# Main.net
KiCad netlist of a schematic drawn in Altium Designer
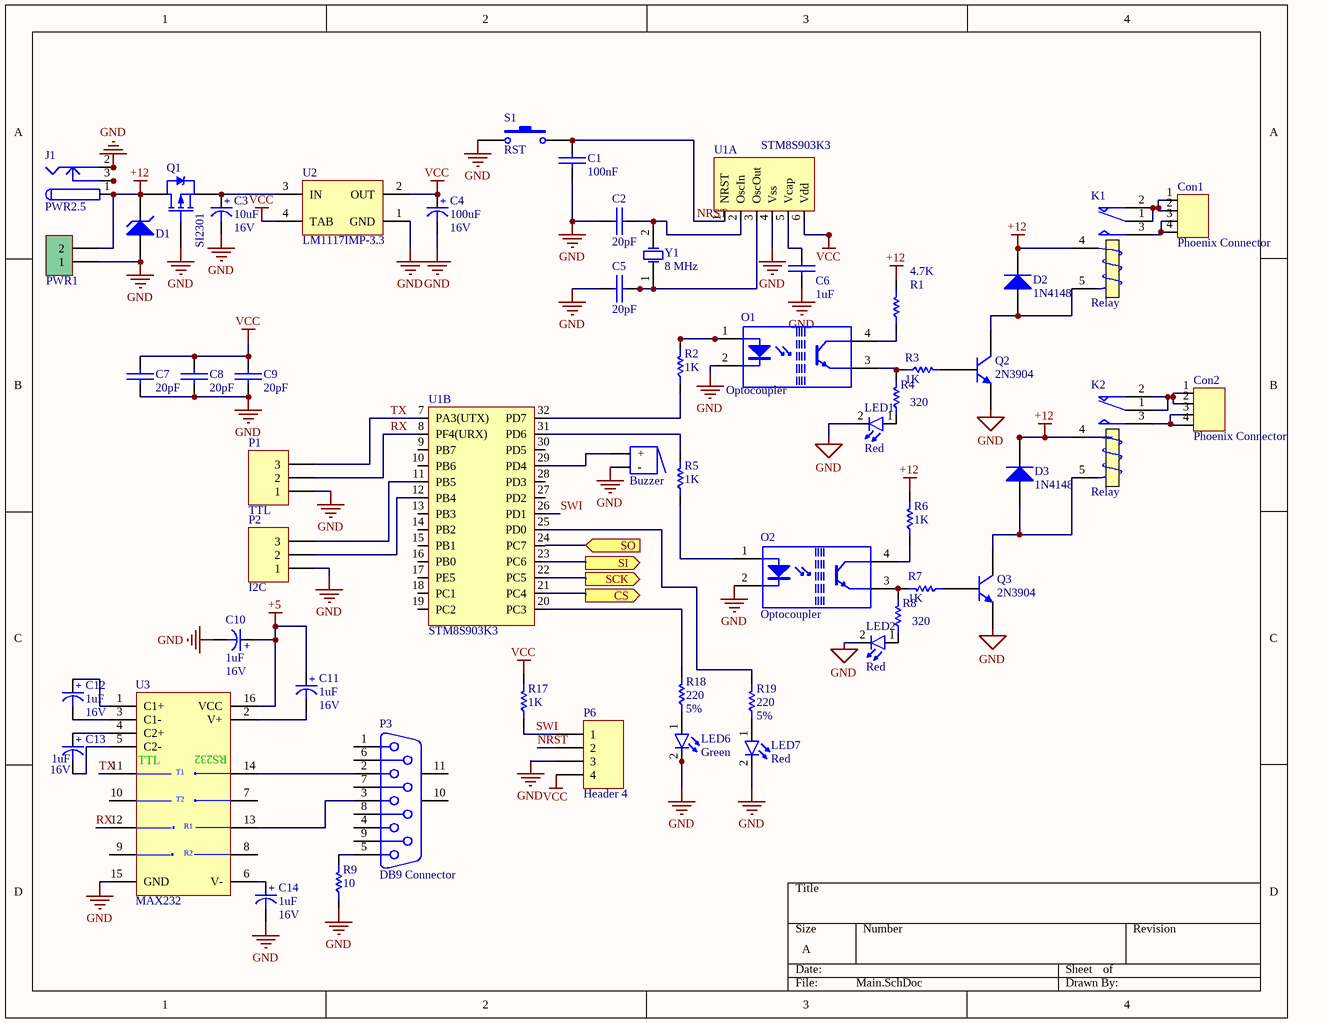
[diagram p0: Main.SchDoc]

(export (version "E")
  (design (tool "Eeschema 10.0.6"))
  (components
    (comp (ref "Buzzer")
      (value "Buzzer")
      (footprint "BUZZER")
      (fields (field (name "DESIGNER") "Seyed Mohsen Ghasemain"))
      (libsource (lib "usefully_Library") (part "Buzzer"))
    )
    (comp (ref "C1")
      (value "100nF")
      (footprint "SMD_CAP_1206")
      (description "Bipolar Capacitor")
      (fields (field (name "VOLTAGE") "100V") (field (name "DESIGNER") "Saeid Jorablo"))
      (libsource (lib "My_Library") (part "Cap-Bipolar"))
    )
    (comp (ref "C2")
      (value "20pF")
      (footprint "SMD_CAP_1206")
      (description "Bipolar Capacitor")
      (fields (field (name "VOLTAGE") "100V") (field (name "DESIGNER") "Saeid Jorablo"))
      (libsource (lib "My_Library") (part "Cap-Bipolar"))
    )
    (comp (ref "C3")
      (value "10uF")
      (footprint "CAPP 1206 (3216X18L) Size A")
      (description "Polar Capacitor")
      (fields (field (name "VOLTAGE") "16V") (field (name "DESIGNER") "Saeid Jorablo"))
      (libsource (lib "My_Library") (part "Cap-Polar"))
    )
    (comp (ref "C4")
      (value "100uF")
      (footprint "CAPP 1206 (3216X18L) Size A")
      (description "Polar Capacitor")
      (fields (field (name "VOLTAGE") "16V") (field (name "DESIGNER") "Saeid Jorablo"))
      (libsource (lib "My_Library") (part "Cap-Polar"))
    )
    (comp (ref "C5")
      (value "20pF")
      (footprint "SMD_CAP_1206")
      (description "Bipolar Capacitor")
      (fields (field (name "VOLTAGE") "100V") (field (name "DESIGNER") "Saeid Jorablo"))
      (libsource (lib "My_Library") (part "Cap-Bipolar"))
    )
    (comp (ref "C6")
      (value "1uF")
      (footprint "SMD_CAP_1206")
      (description "Bipolar Capacitor")
      (fields (field (name "VOLTAGE") "100V") (field (name "DESIGNER") "Saeid Jorablo"))
      (libsource (lib "My_Library") (part "Cap-Bipolar"))
    )
    (comp (ref "C7")
      (value "20pF")
      (footprint "SMD_CAP_1206")
      (description "Bipolar Capacitor")
      (fields (field (name "VOLTAGE") "100V") (field (name "DESIGNER") "Saeid Jorablo"))
      (libsource (lib "My_Library") (part "Cap-Bipolar"))
    )
    (comp (ref "C8")
      (value "20pF")
      (footprint "SMD_CAP_1206")
      (description "Bipolar Capacitor")
      (fields (field (name "VOLTAGE") "100V") (field (name "DESIGNER") "Saeid Jorablo"))
      (libsource (lib "My_Library") (part "Cap-Bipolar"))
    )
    (comp (ref "C9")
      (value "20pF")
      (footprint "SMD_CAP_1206")
      (description "Bipolar Capacitor")
      (fields (field (name "VOLTAGE") "100V") (field (name "DESIGNER") "Saeid Jorablo"))
      (libsource (lib "My_Library") (part "Cap-Bipolar"))
    )
    (comp (ref "C10")
      (value "1uF")
      (footprint "cap 01")
      (description "Polar Capacitor")
      (fields (field (name "VOLTAGE") "16V") (field (name "DESIGNER") "Saeid Jorablo"))
      (libsource (lib "My_Library") (part "Cap-Polar"))
    )
    (comp (ref "C11")
      (value "1uF")
      (footprint "cap 01")
      (description "Polar Capacitor")
      (fields (field (name "VOLTAGE") "16V") (field (name "DESIGNER") "Saeid Jorablo"))
      (libsource (lib "My_Library") (part "Cap-Polar"))
    )
    (comp (ref "C12")
      (value "1uF")
      (footprint "cap 01")
      (description "Polar Capacitor")
      (fields (field (name "VOLTAGE") "16V") (field (name "DESIGNER") "Saeid Jorablo"))
      (libsource (lib "My_Library") (part "Cap-Polar"))
    )
    (comp (ref "C13")
      (value "1uF")
      (footprint "cap 01")
      (description "Polar Capacitor")
      (fields (field (name "VOLTAGE") "16V") (field (name "DESIGNER") "Saeid Jorablo"))
      (libsource (lib "My_Library") (part "Cap-Polar"))
    )
    (comp (ref "C14")
      (value "1uF")
      (footprint "CAPP 1206 (3216X18L) Size A")
      (description "Polar Capacitor")
      (fields (field (name "VOLTAGE") "16V") (field (name "DESIGNER") "Saeid Jorablo"))
      (libsource (lib "My_Library") (part "Cap-Polar"))
    )
    (comp (ref "Con1")
      (value "Phoenix Connector")
      (footprint "KF2EDGRC")
      (libsource (lib "JRLib") (part "Phoenix_4"))
    )
    (comp (ref "Con2")
      (value "Phoenix Connector")
      (footprint "KF2EDGRC")
      (libsource (lib "JRLib") (part "Phoenix_4"))
    )
    (comp (ref "D1")
      (value "Diode Zener")
      (footprint "Diode 1W")
      (description "Zener Diode")
      (fields (field (name "VOLTAGE") "13 V") (field (name "DESIGNER") "Saeid Jorablo"))
      (libsource (lib "My_Library") (part "Diode Zener"))
    )
    (comp (ref "D2")
      (value "1N4148")
      (footprint "Diode 1W")
      (description "High Conductance Fast Diode")
      (fields (field (name "PUBLISHER") "Altium Limited"))
      (libsource (lib "My_Library") (part "Diode 1N4148"))
    )
    (comp (ref "D3")
      (value "1N4148")
      (footprint "Diode 1W")
      (description "High Conductance Fast Diode")
      (fields (field (name "PUBLISHER") "Altium Limited"))
      (libsource (lib "My_Library") (part "Diode 1N4148"))
    )
    (comp (ref "J1")
      (value "PWR2.5")
      (footprint "KLD-0202")
      (description "Low Voltage Power Supply Connector")
      (fields (field (name "PUBLISHER") "Altium Limited"))
      (libsource (lib "Miscellaneous Connectors") (part "PWR2.5"))
    )
    (comp (ref "K1")
      (value "Relay")
      (footprint "Relay 15.40x12.10x13.10")
      (description "SPDT Relay")
      (fields (field (name "DESIGNER") "Eng. Saeid Jorablo"))
      (libsource (lib "My_Library") (part "Relay"))
    )
    (comp (ref "K2")
      (value "Relay")
      (footprint "Relay 15.40x12.10x13.10")
      (description "SPDT Relay")
      (fields (field (name "DESIGNER") "Eng. Saeid Jorablo"))
      (libsource (lib "My_Library") (part "Relay"))
    )
    (comp (ref "LED1")
      (value "Red")
      (footprint "LED-3mm")
      (description "LED")
      (fields (field (name "COLOR") "Red") (field (name "DESIGNER") "Saeid Jorablo"))
      (libsource (lib "My_Library") (part "LED"))
    )
    (comp (ref "LED2")
      (value "Red")
      (footprint "LED-3mm")
      (description "LED")
      (fields (field (name "COLOR") "Red") (field (name "DESIGNER") "Saeid Jorablo"))
      (libsource (lib "My_Library") (part "LED"))
    )
    (comp (ref "LED6")
      (value "Green")
      (footprint "LED-5mm")
      (description "LED")
      (fields (field (name "COLOR") "Green") (field (name "DESIGNER") "Saeid Jorablo"))
      (libsource (lib "My_Library") (part "LED"))
    )
    (comp (ref "LED7")
      (value "Red")
      (footprint "LED-5mm")
      (description "LED")
      (fields (field (name "COLOR") "Red") (field (name "DESIGNER") "Saeid Jorablo"))
      (libsource (lib "My_Library") (part "LED"))
    )
    (comp (ref "O1") (value "Optocoupler") (footprint "DIP4") (libsource (lib "JRLib") (part "PC817")))
    (comp (ref "O2") (value "Optocoupler") (footprint "DIP4") (libsource (lib "JRLib") (part "PC817")))
    (comp (ref "P1")
      (value "TTL")
      (footprint "HDR1X3")
      (description "Header, 3-Pin")
      (fields (field (name "PUBLISHER") "Altium Limited"))
      (libsource (lib "Miscellaneous Connectors") (part "Header 3"))
    )
    (comp (ref "P2")
      (value "I2C")
      (footprint "HDR1X3")
      (description "Header, 3-Pin")
      (fields (field (name "PUBLISHER") "Altium Limited"))
      (libsource (lib "Miscellaneous Connectors") (part "Header 3"))
    )
    (comp (ref "P3")
      (value "DB9 Connector")
      (footprint "DB9 Female")
      (description "Receptacle Assembly, 9 Position, Right Angle")
      (fields (field (name "PUBLISHER") "Altium Limited"))
      (libsource (lib "My_Library") (part "DB9 Connector"))
    )
    (comp (ref "P6")
      (value "Header 4")
      (footprint "HDR1X4")
      (description "Header, 4-Pin")
      (fields (field (name "PUBLISHER") "Altium Limited"))
      (libsource (lib "Miscellaneous Connectors") (part "Header 4"))
    )
    (comp (ref "PWR1")
      (value "Phoenix terminal")
      (footprint "Phoenix2")
      (description "Terminal 2 Pin")
      (fields (field (name "DESIGNER") "Seyed Mohsen Ghasemain") (field (name "E-MAIL") "picpars@gmail.com"))
      (libsource (lib "usefully_Library") (part "Phoenix terminal 2"))
    )
    (comp (ref "Q1")
      (value "SI2301")
      (footprint "SOT-23_M")
      (description "P-Channel Power MOSFET")
      (fields (field (name "PUBLISHER") "Altium Limited"))
      (libsource (lib "Miscellaneous Devices") (part "PMOS-2"))
    )
    (comp (ref "Q2")
      (value "2N3904")
      (footprint "SOT23_BEC_N")
      (description "NPN Bipolar Transistor")
      (fields (field (name "PUBLISHER") "Altium Limited"))
      (libsource (lib "My_Library") (part "NPN"))
    )
    (comp (ref "Q3")
      (value "2N3904")
      (footprint "SOT23_BEC_N")
      (description "NPN Bipolar Transistor")
      (fields (field (name "PUBLISHER") "Altium Limited"))
      (libsource (lib "My_Library") (part "NPN"))
    )
    (comp (ref "R1")
      (value "4.7K")
      (footprint "Res-(1/4)")
      (description "Resistor")
      (libsource (lib "My_Library") (part "Resistor"))
    )
    (comp (ref "R2")
      (value "1K")
      (footprint "RES 1206 (3216X08L)")
      (description "Resistor")
      (libsource (lib "My_Library") (part "Resistor"))
    )
    (comp (ref "R3")
      (value "1K")
      (footprint "Res-(1/4)")
      (description "Resistor")
      (libsource (lib "My_Library") (part "Resistor"))
    )
    (comp (ref "R4")
      (value "320")
      (footprint "Res-(1/4)")
      (description "Resistor")
      (libsource (lib "My_Library") (part "Resistor"))
    )
    (comp (ref "R5")
      (value "1K")
      (footprint "RES 1206 (3216X08L)")
      (description "Resistor")
      (libsource (lib "My_Library") (part "Resistor"))
    )
    (comp (ref "R6")
      (value "1K")
      (footprint "Res-(1/4)")
      (description "Resistor")
      (libsource (lib "My_Library") (part "Resistor"))
    )
    (comp (ref "R7")
      (value "1K")
      (footprint "Res-(1/4)")
      (description "Resistor")
      (libsource (lib "My_Library") (part "Resistor"))
    )
    (comp (ref "R8")
      (value "320")
      (footprint "Res-(1/4)")
      (description "Resistor")
      (libsource (lib "My_Library") (part "Resistor"))
    )
    (comp (ref "R9")
      (value "10")
      (footprint "RES 1206 (3216X08L)")
      (description "Resistor")
      (libsource (lib "My_Library") (part "Resistor"))
    )
    (comp (ref "R17")
      (value "1K")
      (footprint "RES 1206 (3216X08L)")
      (description "Resistor")
      (libsource (lib "My_Library") (part "Resistor"))
    )
    (comp (ref "R18")
      (value "220")
      (footprint "RES 1206 (3216X08L)")
      (description "Resistor")
      (fields (field (name "TOLERANCE") "5%"))
      (libsource (lib "My_Library") (part "Resistor"))
    )
    (comp (ref "R19")
      (value "220")
      (footprint "RES 1206 (3216X08L)")
      (description "Resistor")
      (fields (field (name "TOLERANCE") "5%"))
      (libsource (lib "My_Library") (part "Resistor"))
    )
    (comp (ref "S1")
      (value "RST")
      (footprint "Switch - Push to On")
      (description "Push Button Switch")
      (libsource (lib "My_Library") (part "Switch PB"))
    )
    (comp (ref "U1")
      (value "STM8S903K3")
      (footprint "CQFP80P-32N")
      (description "STM8S903K3 8 bit Microcontroller")
      (libsource (lib "JRLib") (part "STM8S903K3"))
    )
    (comp (ref "U2")
      (value "LM1117IMP-3.3")
      (footprint "MP04A_N")
      (description "x.x Volt, 800mA Low-Dropout Linear Regulator, 4-pin SOT-223")
      (fields
        (field (name "MANUFACTURER") "National Semiconductor")
        (field (name "PUBLISHER") "Altium Limited")
      )
      (libsource (lib "My_Library") (part "LM1117IMP-x.x"))
    )
    (comp (ref "U3")
      (value "MAX232")
      (footprint "SO-16")
      (description "+5V Powered, Multi-Channel RS-232 Driver/Receiver")
      (fields (field (name "COMPONENTAUTHOR") "Saeid Jorablo"))
      (libsource (lib "My_Library") (part "MAX232"))
    )
    (comp (ref "Y1")
      (value "8 MHz")
      (footprint "XTAL Small")
      (description "XTAL Crystal")
      (libsource (lib "My_Library") (part "XTAL"))
    )
  )
  (nets
    (net (code "1") (name "+5") (class "Default")
      (node (ref "C10") (pin "1") (pinfunction "+_1") (pintype "passive"))
      (node (ref "C11") (pin "1") (pinfunction "+_1") (pintype "passive"))
      (node (ref "U3") (pin "16") (pinfunction "VCC_16") (pintype "power_in"))
    )
    (net (code "2") (name "+12") (class "Default")
      (node (ref "D1") (pin "2") (pinfunction "K_2") (pintype "passive"))
      (node (ref "D2") (pin "2") (pinfunction "K_2") (pintype "passive"))
      (node (ref "D3") (pin "2") (pinfunction "K_2") (pintype "passive"))
      (node (ref "J1") (pin "1") (pinfunction "1_1") (pintype "power_in"))
      (node (ref "J1") (pin "1A") (pinfunction "1A_1A") (pintype "power_in"))
      (node (ref "J1") (pin "1B") (pinfunction "1B_1B") (pintype "power_in"))
      (node (ref "K1") (pin "4") (pinfunction "T1_4") (pintype "passive"))
      (node (ref "K2") (pin "4") (pinfunction "T1_4") (pintype "passive"))
      (node (ref "PWR1") (pin "2") (pinfunction "2_2") (pintype "passive"))
      (node (ref "Q1") (pin "2") (pinfunction "D_2") (pintype "passive"))
      (node (ref "R1") (pin "2") (pinfunction "2_2") (pintype "passive"))
      (node (ref "R6") (pin "2") (pinfunction "2_2") (pintype "passive"))
    )
    (net (code "3") (name "/CS") (class "Default")
      (node (ref "U1") (pin "21") (pinfunction "PC4_21") (pintype "passive"))
    )
    (net (code "4") (name "/NRST") (class "Default")
      (node (ref "C1") (pin "1") (pinfunction "+_1") (pintype "passive"))
      (node (ref "P6") (pin "2") (pinfunction "2_2") (pintype "passive"))
      (node (ref "S1") (pin "2") (pinfunction "2_2") (pintype "passive"))
      (node (ref "U1") (pin "1") (pinfunction "NRST_1") (pintype "passive"))
    )
    (net (code "5") (name "/RX") (class "Default")
      (node (ref "P1") (pin "2") (pinfunction "2_2") (pintype "passive"))
      (node (ref "U1") (pin "8") (pinfunction "PF4(URX)_8") (pintype "passive"))
      (node (ref "U3") (pin "12") (pinfunction "R1OUT_12") (pintype "passive"))
    )
    (net (code "6") (name "/SCK") (class "Default")
      (node (ref "U1") (pin "22") (pinfunction "PC5_22") (pintype "passive"))
    )
    (net (code "7") (name "/SI") (class "Default")
      (node (ref "U1") (pin "23") (pinfunction "PC6_23") (pintype "passive"))
    )
    (net (code "8") (name "/SO") (class "Default")
      (node (ref "U1") (pin "24") (pinfunction "PC7_24") (pintype "passive"))
    )
    (net (code "9") (name "/SWI") (class "Default")
      (node (ref "P6") (pin "1") (pinfunction "1_1") (pintype "passive"))
      (node (ref "R17") (pin "1") (pinfunction "1_1") (pintype "passive"))
      (node (ref "U1") (pin "26") (pinfunction "PD1_26") (pintype "passive"))
    )
    (net (code "10") (name "/TX") (class "Default")
      (node (ref "P1") (pin "3") (pinfunction "3_3") (pintype "passive"))
      (node (ref "U1") (pin "7") (pinfunction "PA3(UTX)_7") (pintype "passive"))
      (node (ref "U3") (pin "11") (pinfunction "T1IN_11") (pintype "passive"))
    )
    (net (code "11") (name "GND") (class "Default")
      (node (ref "Buzzer") (pin "2") (pinfunction "-_2") (pintype "passive"))
      (node (ref "C1") (pin "2") (pinfunction "-_2") (pintype "passive"))
      (node (ref "C10") (pin "2") (pinfunction "-_2") (pintype "passive"))
      (node (ref "C14") (pin "2") (pinfunction "-_2") (pintype "passive"))
      (node (ref "C2") (pin "1") (pinfunction "+_1") (pintype "passive"))
      (node (ref "C3") (pin "2") (pinfunction "-_2") (pintype "passive"))
      (node (ref "C4") (pin "2") (pinfunction "-_2") (pintype "passive"))
      (node (ref "C5") (pin "1") (pinfunction "+_1") (pintype "passive"))
      (node (ref "C6") (pin "1") (pinfunction "+_1") (pintype "passive"))
      (node (ref "C7") (pin "1") (pinfunction "+_1") (pintype "passive"))
      (node (ref "C8") (pin "1") (pinfunction "+_1") (pintype "passive"))
      (node (ref "C9") (pin "1") (pinfunction "+_1") (pintype "passive"))
      (node (ref "D1") (pin "1") (pinfunction "A_1") (pintype "passive"))
      (node (ref "J1") (pin "2") (pinfunction "2_2") (pintype "power_in"))
      (node (ref "J1") (pin "2A") (pinfunction "2A_2A") (pintype "power_in"))
      (node (ref "J1") (pin "2B") (pinfunction "2B_2B") (pintype "power_in"))
      (node (ref "LED1") (pin "2") (pinfunction "K_2") (pintype "passive"))
      (node (ref "LED2") (pin "2") (pinfunction "K_2") (pintype "passive"))
      (node (ref "LED6") (pin "2") (pinfunction "K_2") (pintype "passive"))
      (node (ref "LED7") (pin "2") (pinfunction "K_2") (pintype "passive"))
      (node (ref "O1") (pin "2") (pinfunction "K_2") (pintype "passive"))
      (node (ref "O2") (pin "2") (pinfunction "K_2") (pintype "passive"))
      (node (ref "P1") (pin "1") (pinfunction "1_1") (pintype "passive"))
      (node (ref "P2") (pin "1") (pinfunction "1_1") (pintype "passive"))
      (node (ref "P6") (pin "3") (pinfunction "3_3") (pintype "passive"))
      (node (ref "PWR1") (pin "1") (pinfunction "1_1") (pintype "passive"))
      (node (ref "Q1") (pin "1") (pinfunction "G_1") (pintype "passive"))
      (node (ref "Q2") (pin "2") (pinfunction "E_2") (pintype "passive"))
      (node (ref "Q3") (pin "2") (pinfunction "E_2") (pintype "passive"))
      (node (ref "R9") (pin "1") (pinfunction "1_1") (pintype "passive"))
      (node (ref "S1") (pin "1") (pinfunction "1_1") (pintype "passive"))
      (node (ref "U1") (pin "4") (pinfunction "Vss_4") (pintype "passive"))
      (node (ref "U2") (pin "1") (pinfunction "GND_1") (pintype "power_in"))
      (node (ref "U3") (pin "15") (pinfunction "GND_15") (pintype "power_in"))
    )
    (net (code "12") (name "Net-(Buzzer-+)") (class "Default")
      (node (ref "Buzzer") (pin "1") (pinfunction "+_1") (pintype "passive"))
      (node (ref "U1") (pin "29") (pinfunction "PD4_29") (pintype "passive"))
    )
    (net (code "13") (name "Net-(C2--)") (class "Default")
      (node (ref "C2") (pin "2") (pinfunction "-_2") (pintype "passive"))
      (node (ref "U1") (pin "2") (pinfunction "OscIn_2") (pintype "passive"))
      (node (ref "Y1") (pin "2") (pinfunction "OSC2_2") (pintype "passive"))
    )
    (net (code "14") (name "Net-(C3-+)") (class "Default")
      (node (ref "C3") (pin "1") (pinfunction "+_1") (pintype "passive"))
      (node (ref "Q1") (pin "3") (pinfunction "S_3") (pintype "passive"))
      (node (ref "U2") (pin "3") (pinfunction "IN_3") (pintype "power_in"))
    )
    (net (code "15") (name "Net-(C5--)") (class "Default")
      (node (ref "C5") (pin "2") (pinfunction "-_2") (pintype "passive"))
      (node (ref "U1") (pin "3") (pinfunction "OscOut_3") (pintype "passive"))
      (node (ref "Y1") (pin "1") (pinfunction "OSC1_1") (pintype "passive"))
    )
    (net (code "16") (name "Net-(C6--)") (class "Default")
      (node (ref "C6") (pin "2") (pinfunction "-_2") (pintype "passive"))
      (node (ref "U1") (pin "5") (pinfunction "Vcap_5") (pintype "passive"))
    )
    (net (code "17") (name "Net-(C11--)") (class "Default")
      (node (ref "C11") (pin "2") (pinfunction "-_2") (pintype "passive"))
      (node (ref "U3") (pin "2") (pinfunction "V+_2") (pintype "passive"))
    )
    (net (code "18") (name "Net-(C12-+)") (class "Default")
      (node (ref "C12") (pin "1") (pinfunction "+_1") (pintype "passive"))
      (node (ref "U3") (pin "1") (pinfunction "C1+_1") (pintype "passive"))
    )
    (net (code "19") (name "Net-(C12--)") (class "Default")
      (node (ref "C12") (pin "2") (pinfunction "-_2") (pintype "passive"))
      (node (ref "U3") (pin "3") (pinfunction "C1-_3") (pintype "passive"))
    )
    (net (code "20") (name "Net-(C13-+)") (class "Default")
      (node (ref "C13") (pin "1") (pinfunction "+_1") (pintype "passive"))
      (node (ref "U3") (pin "4") (pinfunction "C2+_4") (pintype "passive"))
    )
    (net (code "21") (name "Net-(C13--)") (class "Default")
      (node (ref "C13") (pin "2") (pinfunction "-_2") (pintype "passive"))
      (node (ref "U3") (pin "5") (pinfunction "C2-_5") (pintype "passive"))
    )
    (net (code "22") (name "Net-(C14-+)") (class "Default")
      (node (ref "C14") (pin "1") (pinfunction "+_1") (pintype "passive"))
      (node (ref "U3") (pin "6") (pinfunction "V-_6") (pintype "passive"))
    )
    (net (code "23") (name "Net-(D2-A)") (class "Default")
      (node (ref "D2") (pin "1") (pinfunction "A_1") (pintype "passive"))
      (node (ref "K1") (pin "5") (pinfunction "T2_5") (pintype "passive"))
      (node (ref "Q2") (pin "3") (pinfunction "C_3") (pintype "passive"))
    )
    (net (code "24") (name "Net-(D3-A)") (class "Default")
      (node (ref "D3") (pin "1") (pinfunction "A_1") (pintype "passive"))
      (node (ref "K2") (pin "5") (pinfunction "T2_5") (pintype "passive"))
      (node (ref "Q3") (pin "3") (pinfunction "C_3") (pintype "passive"))
    )
    (net (code "25") (name "Net-(J1-Pad3)") (class "Default")
      (node (ref "J1") (pin "3") (pinfunction "3_3") (pintype "power_in"))
      (node (ref "J1") (pin "3A") (pinfunction "3A_3A") (pintype "power_in"))
      (node (ref "J1") (pin "3B") (pinfunction "3B_3B") (pintype "power_in"))
    )
    (net (code "26") (name "Net-(K1-COM)") (class "Default")
      (node (ref "Con1") (pin "1") (pinfunction "1_1") (pintype "passive"))
      (node (ref "Con1") (pin "2") (pinfunction "2_2") (pintype "passive"))
      (node (ref "K1") (pin "1") (pinfunction "COM_1") (pintype "passive"))
      (node (ref "K1") (pin "2") (pinfunction "NC_2") (pintype "passive"))
    )
    (net (code "27") (name "Net-(K1-NO)") (class "Default")
      (node (ref "Con1") (pin "3") (pinfunction "3_3") (pintype "passive"))
      (node (ref "Con1") (pin "4") (pinfunction "4_4") (pintype "passive"))
      (node (ref "K1") (pin "3") (pinfunction "NO_3") (pintype "passive"))
    )
    (net (code "28") (name "Net-(K2-COM)") (class "Default")
      (node (ref "Con2") (pin "1") (pinfunction "1_1") (pintype "passive"))
      (node (ref "Con2") (pin "2") (pinfunction "2_2") (pintype "passive"))
      (node (ref "K2") (pin "1") (pinfunction "COM_1") (pintype "passive"))
      (node (ref "K2") (pin "2") (pinfunction "NC_2") (pintype "passive"))
    )
    (net (code "29") (name "Net-(K2-NO)") (class "Default")
      (node (ref "Con2") (pin "3") (pinfunction "3_3") (pintype "passive"))
      (node (ref "Con2") (pin "4") (pinfunction "4_4") (pintype "passive"))
      (node (ref "K2") (pin "3") (pinfunction "NO_3") (pintype "passive"))
    )
    (net (code "30") (name "Net-(LED1-A)") (class "Default")
      (node (ref "LED1") (pin "1") (pinfunction "A_1") (pintype "passive"))
      (node (ref "R4") (pin "1") (pinfunction "1_1") (pintype "passive"))
    )
    (net (code "31") (name "Net-(LED2-A)") (class "Default")
      (node (ref "LED2") (pin "1") (pinfunction "A_1") (pintype "passive"))
      (node (ref "R8") (pin "1") (pinfunction "1_1") (pintype "passive"))
    )
    (net (code "32") (name "Net-(LED6-A)") (class "Default")
      (node (ref "LED6") (pin "1") (pinfunction "A_1") (pintype "passive"))
      (node (ref "R18") (pin "1") (pinfunction "1_1") (pintype "passive"))
    )
    (net (code "33") (name "Net-(LED7-A)") (class "Default")
      (node (ref "LED7") (pin "1") (pinfunction "A_1") (pintype "passive"))
      (node (ref "R19") (pin "1") (pinfunction "1_1") (pintype "passive"))
    )
    (net (code "34") (name "Net-(O1-A)") (class "Default")
      (node (ref "O1") (pin "1") (pinfunction "A_1") (pintype "passive"))
      (node (ref "R2") (pin "2") (pinfunction "2_2") (pintype "passive"))
    )
    (net (code "35") (name "Net-(O1-C)") (class "Default")
      (node (ref "O1") (pin "4") (pinfunction "C_4") (pintype "passive"))
      (node (ref "R1") (pin "1") (pinfunction "1_1") (pintype "passive"))
    )
    (net (code "36") (name "Net-(O1-E)") (class "Default")
      (node (ref "O1") (pin "3") (pinfunction "E_3") (pintype "passive"))
      (node (ref "R3") (pin "1") (pinfunction "1_1") (pintype "passive"))
      (node (ref "R4") (pin "2") (pinfunction "2_2") (pintype "passive"))
    )
    (net (code "37") (name "Net-(O2-A)") (class "Default")
      (node (ref "O2") (pin "1") (pinfunction "A_1") (pintype "passive"))
      (node (ref "R5") (pin "1") (pinfunction "1_1") (pintype "passive"))
    )
    (net (code "38") (name "Net-(O2-C)") (class "Default")
      (node (ref "O2") (pin "4") (pinfunction "C_4") (pintype "passive"))
      (node (ref "R6") (pin "1") (pinfunction "1_1") (pintype "passive"))
    )
    (net (code "39") (name "Net-(O2-E)") (class "Default")
      (node (ref "O2") (pin "3") (pinfunction "E_3") (pintype "passive"))
      (node (ref "R7") (pin "2") (pinfunction "2_2") (pintype "passive"))
      (node (ref "R8") (pin "2") (pinfunction "2_2") (pintype "passive"))
    )
    (net (code "40") (name "Net-(P3-Pad5)") (class "Default")
      (node (ref "P3") (pin "5") (pinfunction "5_5") (pintype "passive"))
      (node (ref "R9") (pin "2") (pinfunction "2_2") (pintype "passive"))
    )
    (net (code "41") (name "Net-(Q2-B)") (class "Default")
      (node (ref "Q2") (pin "1") (pinfunction "B_1") (pintype "passive"))
      (node (ref "R3") (pin "2") (pinfunction "2_2") (pintype "passive"))
    )
    (net (code "42") (name "Net-(Q3-B)") (class "Default")
      (node (ref "Q3") (pin "1") (pinfunction "B_1") (pintype "passive"))
      (node (ref "R7") (pin "1") (pinfunction "1_1") (pintype "passive"))
    )
    (net (code "43") (name "Net-(U1B-PB4)") (class "Default")
      (node (ref "P2") (pin "2") (pinfunction "2_2") (pintype "passive"))
      (node (ref "U1") (pin "12") (pinfunction "PB4_12") (pintype "passive"))
    )
    (net (code "44") (name "Net-(U1B-PB5)") (class "Default")
      (node (ref "P2") (pin "3") (pinfunction "3_3") (pintype "passive"))
      (node (ref "U1") (pin "11") (pinfunction "PB5_11") (pintype "passive"))
    )
    (net (code "45") (name "Net-(U1B-PC3)") (class "Default")
      (node (ref "R18") (pin "2") (pinfunction "2_2") (pintype "passive"))
      (node (ref "U1") (pin "20") (pinfunction "PC3_20") (pintype "passive"))
    )
    (net (code "46") (name "Net-(U1B-PD0)") (class "Default")
      (node (ref "R19") (pin "2") (pinfunction "2_2") (pintype "passive"))
      (node (ref "U1") (pin "25") (pinfunction "PD0_25") (pintype "passive"))
    )
    (net (code "47") (name "Net-(U1B-PD6)") (class "Default")
      (node (ref "R5") (pin "2") (pinfunction "2_2") (pintype "passive"))
      (node (ref "U1") (pin "31") (pinfunction "PD6_31") (pintype "passive"))
    )
    (net (code "48") (name "Net-(U1B-PD7)") (class "Default")
      (node (ref "R2") (pin "1") (pinfunction "1_1") (pintype "passive"))
      (node (ref "U1") (pin "32") (pinfunction "PD7_32") (pintype "passive"))
    )
    (net (code "49") (name "Net-(U3-R1IN)") (class "Default")
      (node (ref "P3") (pin "3") (pinfunction "3_3") (pintype "passive"))
      (node (ref "U3") (pin "13") (pinfunction "R1IN_13") (pintype "passive"))
    )
    (net (code "50") (name "Net-(U3-T1OUT)") (class "Default")
      (node (ref "P3") (pin "2") (pinfunction "2_2") (pintype "passive"))
      (node (ref "U3") (pin "14") (pinfunction "T1OUT_14") (pintype "passive"))
    )
    (net (code "51") (name "VCC") (class "Default")
      (node (ref "C4") (pin "1") (pinfunction "+_1") (pintype "passive"))
      (node (ref "C7") (pin "2") (pinfunction "-_2") (pintype "passive"))
      (node (ref "C8") (pin "2") (pinfunction "-_2") (pintype "passive"))
      (node (ref "C9") (pin "2") (pinfunction "-_2") (pintype "passive"))
      (node (ref "P6") (pin "4") (pinfunction "4_4") (pintype "passive"))
      (node (ref "R17") (pin "2") (pinfunction "2_2") (pintype "passive"))
      (node (ref "U1") (pin "6") (pinfunction "Vdd_6") (pintype "passive"))
      (node (ref "U2") (pin "2") (pinfunction "OUT_2") (pintype "power_in"))
      (node (ref "U2") (pin "4") (pinfunction "TAB_4") (pintype "power_in"))
    )
    (net (code "52") (name "unconnected-(P3-MH1-Pad10)") (class "Default")
      (node (ref "P3") (pin "10") (pinfunction "MH1_10") (pintype "passive"))
    )
    (net (code "53") (name "unconnected-(P3-MH2-Pad11)") (class "Default")
      (node (ref "P3") (pin "11") (pinfunction "MH2_11") (pintype "passive"))
    )
    (net (code "54") (name "unconnected-(P3-Pad1)") (class "Default")
      (node (ref "P3") (pin "1") (pinfunction "1_1") (pintype "passive"))
    )
    (net (code "55") (name "unconnected-(P3-Pad4)") (class "Default")
      (node (ref "P3") (pin "4") (pinfunction "4_4") (pintype "passive"))
    )
    (net (code "56") (name "unconnected-(P3-Pad6)") (class "Default")
      (node (ref "P3") (pin "6") (pinfunction "6_6") (pintype "passive"))
    )
    (net (code "57") (name "unconnected-(P3-Pad7)") (class "Default")
      (node (ref "P3") (pin "7") (pinfunction "7_7") (pintype "passive"))
    )
    (net (code "58") (name "unconnected-(P3-Pad8)") (class "Default")
      (node (ref "P3") (pin "8") (pinfunction "8_8") (pintype "passive"))
    )
    (net (code "59") (name "unconnected-(P3-Pad9)") (class "Default")
      (node (ref "P3") (pin "9") (pinfunction "9_9") (pintype "passive"))
    )
    (net (code "60") (name "unconnected-(U1B-PB0-Pad16)") (class "Default")
      (node (ref "U1") (pin "16") (pinfunction "PB0_16") (pintype "passive"))
    )
    (net (code "61") (name "unconnected-(U1B-PB1-Pad15)") (class "Default")
      (node (ref "U1") (pin "15") (pinfunction "PB1_15") (pintype "passive"))
    )
    (net (code "62") (name "unconnected-(U1B-PB2-Pad14)") (class "Default")
      (node (ref "U1") (pin "14") (pinfunction "PB2_14") (pintype "passive"))
    )
    (net (code "63") (name "unconnected-(U1B-PB3-Pad13)") (class "Default")
      (node (ref "U1") (pin "13") (pinfunction "PB3_13") (pintype "passive"))
    )
    (net (code "64") (name "unconnected-(U1B-PB6-Pad10)") (class "Default")
      (node (ref "U1") (pin "10") (pinfunction "PB6_10") (pintype "passive"))
    )
    (net (code "65") (name "unconnected-(U1B-PB7-Pad9)") (class "Default")
      (node (ref "U1") (pin "9") (pinfunction "PB7_9") (pintype "passive"))
    )
    (net (code "66") (name "unconnected-(U1B-PC1-Pad18)") (class "Default")
      (node (ref "U1") (pin "18") (pinfunction "PC1_18") (pintype "passive"))
    )
    (net (code "67") (name "unconnected-(U1B-PC2-Pad19)") (class "Default")
      (node (ref "U1") (pin "19") (pinfunction "PC2_19") (pintype "passive"))
    )
    (net (code "68") (name "unconnected-(U1B-PD2-Pad27)") (class "Default")
      (node (ref "U1") (pin "27") (pinfunction "PD2_27") (pintype "passive"))
    )
    (net (code "69") (name "unconnected-(U1B-PD3-Pad28)") (class "Default")
      (node (ref "U1") (pin "28") (pinfunction "PD3_28") (pintype "passive"))
    )
    (net (code "70") (name "unconnected-(U1B-PD5-Pad30)") (class "Default")
      (node (ref "U1") (pin "30") (pinfunction "PD5_30") (pintype "passive"))
    )
    (net (code "71") (name "unconnected-(U1B-PE5-Pad17)") (class "Default")
      (node (ref "U1") (pin "17") (pinfunction "PE5_17") (pintype "passive"))
    )
    (net (code "72") (name "unconnected-(U3-R2IN-Pad8)") (class "Default")
      (node (ref "U3") (pin "8") (pinfunction "R2IN_8") (pintype "passive"))
    )
    (net (code "73") (name "unconnected-(U3-R2OUT-Pad9)") (class "Default")
      (node (ref "U3") (pin "9") (pinfunction "R2OUT_9") (pintype "passive"))
    )
    (net (code "74") (name "unconnected-(U3-T2IN-Pad10)") (class "Default")
      (node (ref "U3") (pin "10") (pinfunction "T2IN_10") (pintype "passive"))
    )
    (net (code "75") (name "unconnected-(U3-T2OUT-Pad7)") (class "Default")
      (node (ref "U3") (pin "7") (pinfunction "T2OUT_7") (pintype "passive"))
    )
  )
)
